# schematic1.net
KiCad netlist of a schematic drawn in EAGLE
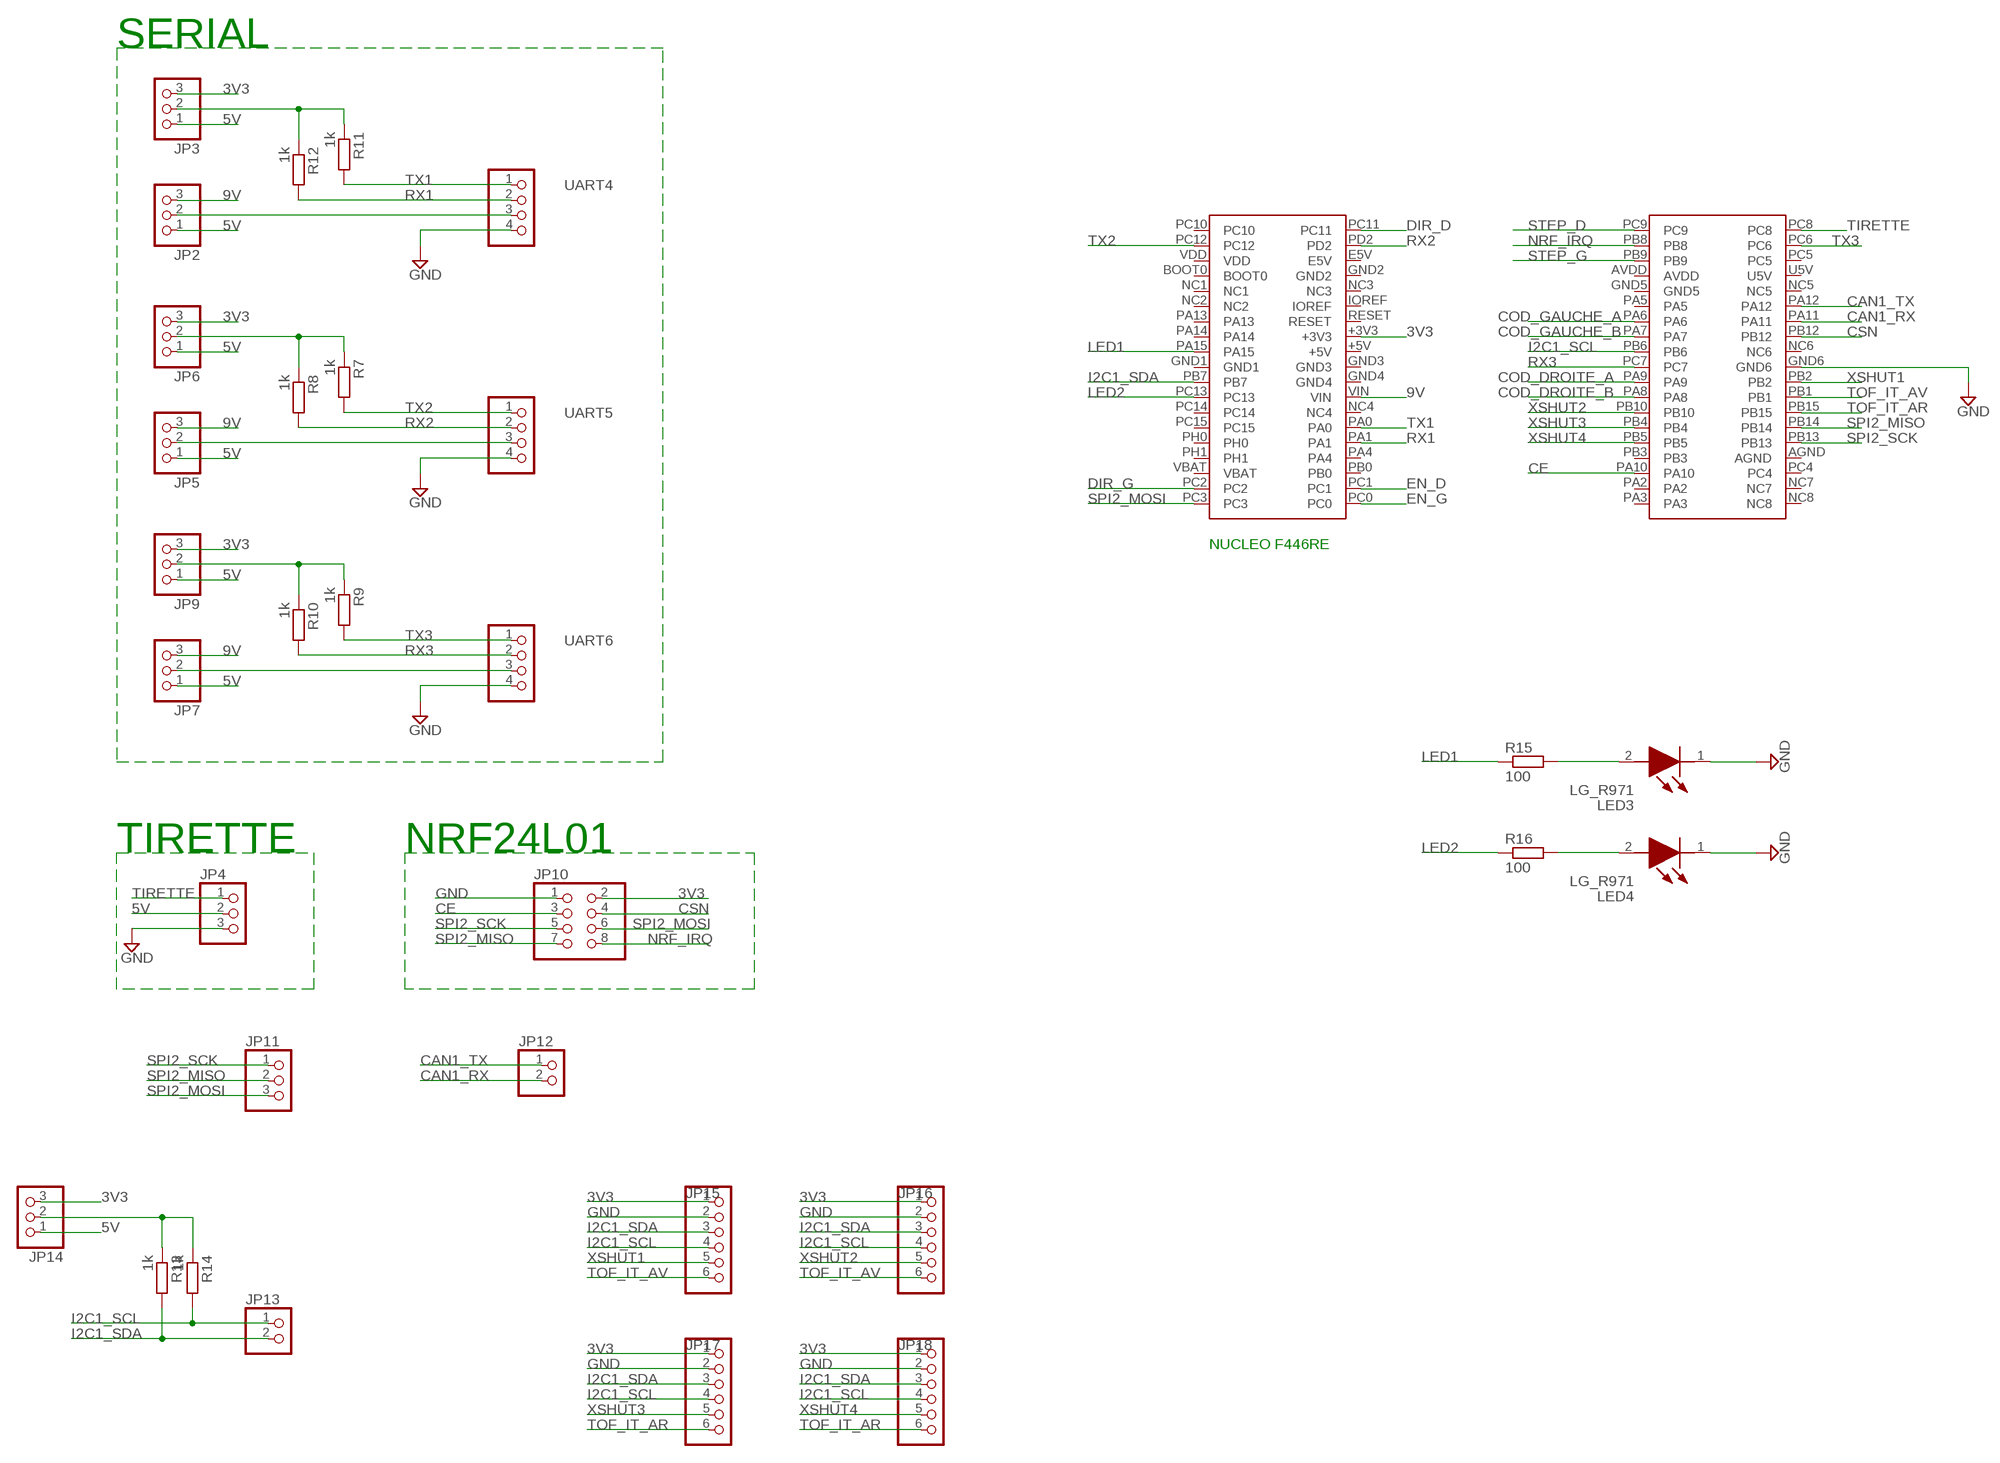
[diagram p0: schematic, sheet 1]
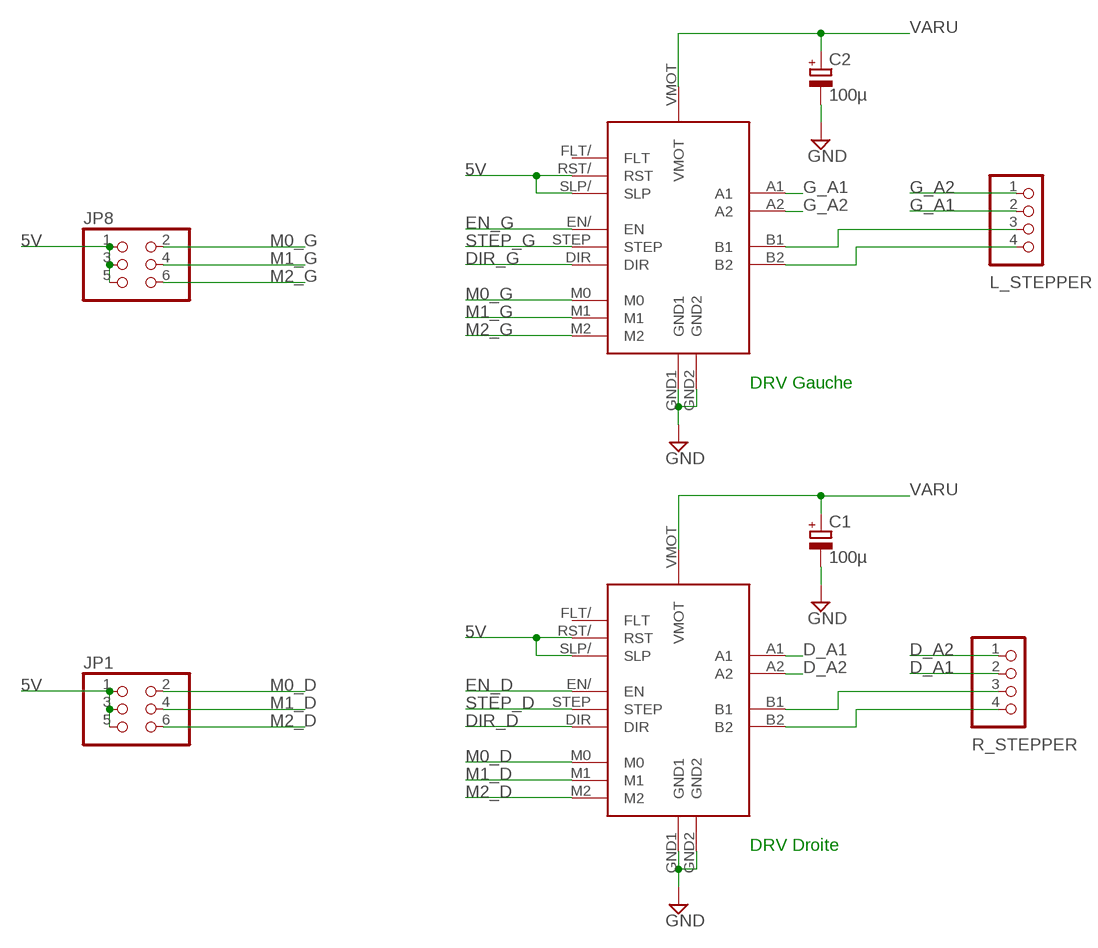
[diagram p1: schematic, sheet 2]
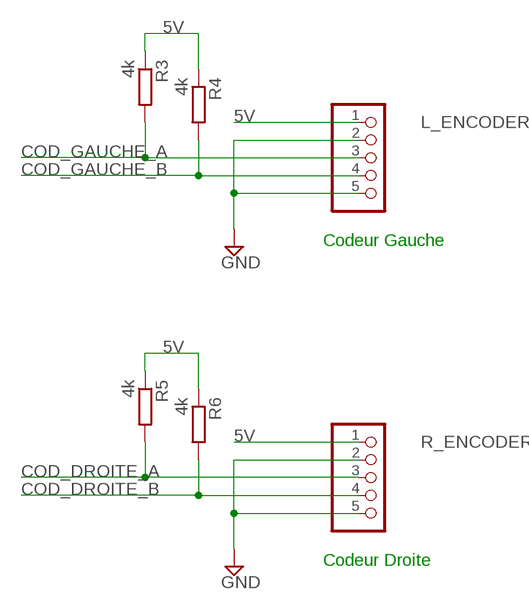
[diagram p2: schematic, sheet 3]
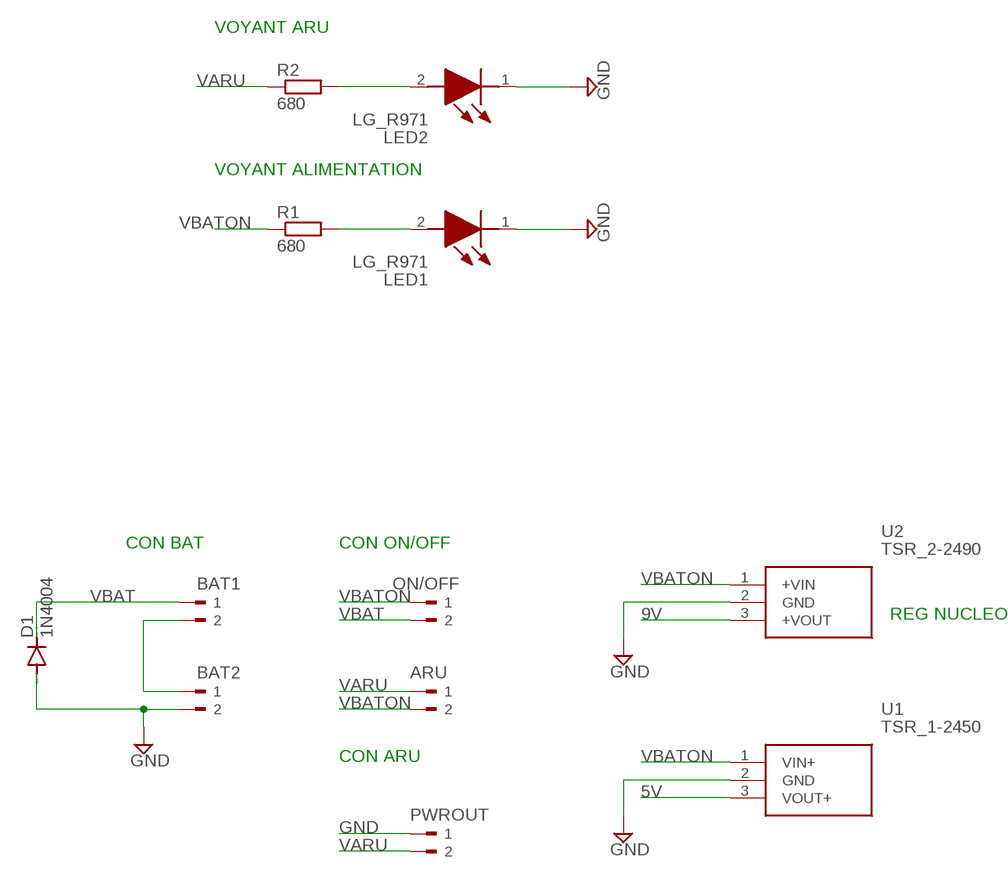
[diagram p3: schematic, sheet 4]

(export (version "E")
  (design (tool "Eeschema 10.0.6"))
  (components
    (comp (ref "JP2")
      (value "PINHD-1X3")
      (footprint "eagle-import:1X03")
      (libsource (lib "eagle-import") (part "PINHD-1X3"))
    )
    (comp (ref "JP3")
      (value "PINHD-1X3")
      (footprint "eagle-import:1X03")
      (libsource (lib "eagle-import") (part "PINHD-1X3"))
    )
    (comp (ref "JP4")
      (value "PINHD-1X3")
      (footprint "eagle-import:1X03")
      (libsource (lib "eagle-import") (part "PINHD-1X3"))
    )
    (comp (ref "JP5")
      (value "PINHD-1X3")
      (footprint "eagle-import:1X03")
      (libsource (lib "eagle-import") (part "PINHD-1X3"))
    )
    (comp (ref "JP6")
      (value "PINHD-1X3")
      (footprint "eagle-import:1X03")
      (libsource (lib "eagle-import") (part "PINHD-1X3"))
    )
    (comp (ref "JP7")
      (value "PINHD-1X3")
      (footprint "eagle-import:1X03")
      (libsource (lib "eagle-import") (part "PINHD-1X3"))
    )
    (comp (ref "JP9")
      (value "PINHD-1X3")
      (footprint "eagle-import:1X03")
      (libsource (lib "eagle-import") (part "PINHD-1X3"))
    )
    (comp (ref "JP10")
      (value "PINHD-2X4")
      (footprint "eagle-import:2X04")
      (libsource (lib "eagle-import") (part "PINHD-2X4"))
    )
    (comp (ref "JP11")
      (value "PINHD-1X3")
      (footprint "eagle-import:1X03")
      (libsource (lib "eagle-import") (part "PINHD-1X3"))
    )
    (comp (ref "JP12")
      (value "PINHD-1X2")
      (footprint "eagle-import:1X02")
      (libsource (lib "eagle-import") (part "PINHD-1X2"))
    )
    (comp (ref "JP13")
      (value "PINHD-1X2")
      (footprint "eagle-import:1X02")
      (libsource (lib "eagle-import") (part "PINHD-1X2"))
    )
    (comp (ref "JP14")
      (value "PINHD-1X3")
      (footprint "eagle-import:1X03")
      (libsource (lib "eagle-import") (part "PINHD-1X3"))
    )
    (comp (ref "JP15")
      (value "PINHD-1X6")
      (footprint "eagle-import:1X06")
      (libsource (lib "eagle-import") (part "PINHD-1X6"))
    )
    (comp (ref "JP16")
      (value "PINHD-1X6")
      (footprint "eagle-import:1X06")
      (libsource (lib "eagle-import") (part "PINHD-1X6"))
    )
    (comp (ref "JP17")
      (value "PINHD-1X6")
      (footprint "eagle-import:1X06")
      (libsource (lib "eagle-import") (part "PINHD-1X6"))
    )
    (comp (ref "JP18")
      (value "PINHD-1X6")
      (footprint "eagle-import:1X06")
      (libsource (lib "eagle-import") (part "PINHD-1X6"))
    )
    (comp (ref "LED3")
      (value "LG_R971")
      (footprint "eagle-import:LEDC2012X90N")
      (fields (field (name "MANUFACTURER_PART_NUMBER") "LG R971") (field (name "RS_PART_NUMBER") "6545773P"))
      (libsource (lib "eagle-import") (part "LG_R971"))
    )
    (comp (ref "LED4")
      (value "LG_R971")
      (footprint "eagle-import:LEDC2012X90N")
      (fields (field (name "MANUFACTURER_PART_NUMBER") "LG R971") (field (name "RS_PART_NUMBER") "6545773P"))
      (libsource (lib "eagle-import") (part "LG_R971"))
    )
    (comp (ref "R7")
      (value "1k")
      (footprint "eagle-import:R0805")
      (libsource (lib "eagle-import") (part "R-EU_R0805"))
    )
    (comp (ref "R8")
      (value "1k")
      (footprint "eagle-import:R0805")
      (libsource (lib "eagle-import") (part "R-EU_R0805"))
    )
    (comp (ref "R9")
      (value "1k")
      (footprint "eagle-import:R0805")
      (libsource (lib "eagle-import") (part "R-EU_R0805"))
    )
    (comp (ref "R10")
      (value "1k")
      (footprint "eagle-import:R0805")
      (libsource (lib "eagle-import") (part "R-EU_R0805"))
    )
    (comp (ref "R11")
      (value "1k")
      (footprint "eagle-import:R0805")
      (libsource (lib "eagle-import") (part "R-EU_R0805"))
    )
    (comp (ref "R12")
      (value "1k")
      (footprint "eagle-import:R0805")
      (libsource (lib "eagle-import") (part "R-EU_R0805"))
    )
    (comp (ref "R13")
      (value "1k")
      (footprint "eagle-import:R0805")
      (libsource (lib "eagle-import") (part "R-EU_R0805"))
    )
    (comp (ref "R14")
      (value "1k")
      (footprint "eagle-import:R0805")
      (libsource (lib "eagle-import") (part "R-EU_R0805"))
    )
    (comp (ref "R15")
      (value "100")
      (footprint "eagle-import:R0805")
      (libsource (lib "eagle-import") (part "R-EU_R0805"))
    )
    (comp (ref "R16")
      (value "100")
      (footprint "eagle-import:R0805")
      (libsource (lib "eagle-import") (part "R-EU_R0805"))
    )
    (comp (ref "U$1")
      (value "NUCLEO_F446RE")
      (footprint "eagle-import:MB1136")
      (libsource (lib "eagle-import") (part "NUCLEO_F446RE"))
    )
    (comp (ref "UART4")
      (value "PINHD-1X4")
      (footprint "eagle-import:1X04")
      (libsource (lib "eagle-import") (part "PINHD-1X4"))
    )
    (comp (ref "UART5")
      (value "PINHD-1X4")
      (footprint "eagle-import:1X04")
      (libsource (lib "eagle-import") (part "PINHD-1X4"))
    )
    (comp (ref "UART6")
      (value "PINHD-1X4")
      (footprint "eagle-import:1X04")
      (libsource (lib "eagle-import") (part "PINHD-1X4"))
    )
    (comp (ref "L_ENCODER")
      (value "PINHD-1X5")
      (footprint "eagle-import:1X05")
      (libsource (lib "eagle-import") (part "PINHD-1X5"))
    )
    (comp (ref "R3")
      (value "4k")
      (footprint "eagle-import:R0805")
      (libsource (lib "eagle-import") (part "R-EU_R0805"))
    )
    (comp (ref "R4")
      (value "4k")
      (footprint "eagle-import:R0805")
      (libsource (lib "eagle-import") (part "R-EU_R0805"))
    )
    (comp (ref "R5")
      (value "4k")
      (footprint "eagle-import:R0805")
      (libsource (lib "eagle-import") (part "R-EU_R0805"))
    )
    (comp (ref "R6")
      (value "4k")
      (footprint "eagle-import:R0805")
      (libsource (lib "eagle-import") (part "R-EU_R0805"))
    )
    (comp (ref "R_ENCODER")
      (value "PINHD-1X5")
      (footprint "eagle-import:1X05")
      (libsource (lib "eagle-import") (part "PINHD-1X5"))
    )
    (comp (ref "ARU")
      (value "180G-2")
      (footprint "eagle-import:180G-2")
      (libsource (lib "eagle-import") (part "180G-2"))
    )
    (comp (ref "BAT1")
      (value "180G-2")
      (footprint "eagle-import:180G-2")
      (libsource (lib "eagle-import") (part "180G-2"))
    )
    (comp (ref "BAT2")
      (value "180G-2")
      (footprint "eagle-import:180G-2")
      (libsource (lib "eagle-import") (part "180G-2"))
    )
    (comp (ref "D1")
      (value "1N4004")
      (footprint "eagle-import:DO41-10")
      (libsource (lib "eagle-import") (part "1N4004"))
    )
    (comp (ref "LED1")
      (value "LG_R971")
      (footprint "eagle-import:LEDC2012X90N")
      (fields (field (name "MANUFACTURER_PART_NUMBER") "LG R971") (field (name "RS_PART_NUMBER") "6545773P"))
      (libsource (lib "eagle-import") (part "LG_R971"))
    )
    (comp (ref "LED2")
      (value "LG_R971")
      (footprint "eagle-import:LEDC2012X90N")
      (fields (field (name "MANUFACTURER_PART_NUMBER") "LG R971") (field (name "RS_PART_NUMBER") "6545773P"))
      (libsource (lib "eagle-import") (part "LG_R971"))
    )
    (comp (ref "ON/OFF")
      (value "180G-2")
      (footprint "eagle-import:180G-2")
      (libsource (lib "eagle-import") (part "180G-2"))
    )
    (comp (ref "PWROUT")
      (value "180G-2")
      (footprint "eagle-import:180G-2")
      (libsource (lib "eagle-import") (part "180G-2"))
    )
    (comp (ref "R1")
      (value "680")
      (footprint "eagle-import:R0805")
      (libsource (lib "eagle-import") (part "R-EU_R0805"))
    )
    (comp (ref "R2")
      (value "680")
      (footprint "eagle-import:R0805")
      (libsource (lib "eagle-import") (part "R-EU_R0805"))
    )
    (comp (ref "U1")
      (value "TSR_1-2450")
      (footprint "eagle-import:TSR-1-24120")
      (fields
        (field (name "MANUFACTURER_PART_NUMBER") "TSR 1-2450")
        (field (name "RS_PART_NUMBER") "6664379P")
      )
      (libsource (lib "eagle-import") (part "TSR_1-2450"))
    )
    (comp (ref "U2")
      (value "TSR_2-2490")
      (footprint "eagle-import:TSR_2-24XX")
      (fields
        (field (name "MANUFACTURER_PART_NUMBER") "TSR 2-2490")
        (field (name "MOUSER_PART_NUMBER") "495-TSR2-2490")
      )
      (libsource (lib "eagle-import") (part "TSR_2-2490"))
    )
    (comp (ref "C1")
      (value "100µ")
      (footprint "eagle-import:E5-6")
      (libsource (lib "eagle-import") (part "CPOL-EUE5-6"))
    )
    (comp (ref "C2")
      (value "100µ")
      (footprint "eagle-import:E5-6")
      (libsource (lib "eagle-import") (part "CPOL-EUE5-6"))
    )
    (comp (ref "JP1")
      (value "PINHD-2X3")
      (footprint "eagle-import:2X03")
      (libsource (lib "eagle-import") (part "PINHD-2X3"))
    )
    (comp (ref "JP8")
      (value "PINHD-2X3")
      (footprint "eagle-import:2X03")
      (libsource (lib "eagle-import") (part "PINHD-2X3"))
    )
    (comp (ref "L_STEPPER")
      (value "PINHD-1X4")
      (footprint "eagle-import:1X04")
      (libsource (lib "eagle-import") (part "PINHD-1X4"))
    )
    (comp (ref "R_STEPPER")
      (value "PINHD-1X4")
      (footprint "eagle-import:1X04")
      (libsource (lib "eagle-import") (part "PINHD-1X4"))
    )
    (comp (ref "U$2")
      (value "POLOLU_DRV8825")
      (footprint "eagle-import:POLOLU_DRV8825")
      (libsource (lib "eagle-import") (part "POLOLU_DRV8825"))
    )
    (comp (ref "U$3")
      (value "POLOLU_DRV8825")
      (footprint "eagle-import:POLOLU_DRV8825")
      (libsource (lib "eagle-import") (part "POLOLU_DRV8825"))
    )
  )
  (nets
    (net (code "1") (name "3V3") (class "Default")
      (node (ref "JP10") (pin "2") (pinfunction "2_2") (pintype "passive"))
      (node (ref "JP14") (pin "3") (pinfunction "3_3") (pintype "passive"))
      (node (ref "JP15") (pin "1") (pinfunction "1_1") (pintype "passive"))
      (node (ref "JP16") (pin "1") (pinfunction "1_1") (pintype "passive"))
      (node (ref "JP17") (pin "1") (pinfunction "1_1") (pintype "passive"))
      (node (ref "JP18") (pin "1") (pinfunction "1_1") (pintype "passive"))
      (node (ref "JP3") (pin "3") (pinfunction "3_3") (pintype "passive"))
      (node (ref "JP6") (pin "3") (pinfunction "3_3") (pintype "passive"))
      (node (ref "JP9") (pin "3") (pinfunction "3_3") (pintype "passive"))
      (node (ref "U$1") (pin "+3V3") (pinfunction "+3V3_+3V3") (pintype "bidirectional"))
    )
    (net (code "2") (name "5V") (class "Default")
      (node (ref "JP1") (pin "1") (pinfunction "1_1") (pintype "passive"))
      (node (ref "JP1") (pin "3") (pinfunction "3_3") (pintype "passive"))
      (node (ref "JP1") (pin "5") (pinfunction "5_5") (pintype "passive"))
      (node (ref "JP14") (pin "1") (pinfunction "1_1") (pintype "passive"))
      (node (ref "JP2") (pin "1") (pinfunction "1_1") (pintype "passive"))
      (node (ref "JP3") (pin "1") (pinfunction "1_1") (pintype "passive"))
      (node (ref "JP4") (pin "2") (pinfunction "2_2") (pintype "passive"))
      (node (ref "JP5") (pin "1") (pinfunction "1_1") (pintype "passive"))
      (node (ref "JP6") (pin "1") (pinfunction "1_1") (pintype "passive"))
      (node (ref "JP7") (pin "1") (pinfunction "1_1") (pintype "passive"))
      (node (ref "JP8") (pin "1") (pinfunction "1_1") (pintype "passive"))
      (node (ref "JP8") (pin "3") (pinfunction "3_3") (pintype "passive"))
      (node (ref "JP8") (pin "5") (pinfunction "5_5") (pintype "passive"))
      (node (ref "JP9") (pin "1") (pinfunction "1_1") (pintype "passive"))
      (node (ref "L_ENCODER") (pin "1") (pinfunction "1_1") (pintype "passive"))
      (node (ref "R3") (pin "1") (pinfunction "1_1") (pintype "passive"))
      (node (ref "R4") (pin "1") (pinfunction "1_1") (pintype "passive"))
      (node (ref "R5") (pin "1") (pinfunction "1_1") (pintype "passive"))
      (node (ref "R6") (pin "1") (pinfunction "1_1") (pintype "passive"))
      (node (ref "R_ENCODER") (pin "1") (pinfunction "1_1") (pintype "passive"))
      (node (ref "U$2") (pin "RST/") (pinfunction "RST_RST/") (pintype "bidirectional"))
      (node (ref "U$2") (pin "SLP/") (pinfunction "SLP_SLP/") (pintype "bidirectional"))
      (node (ref "U$3") (pin "RST/") (pinfunction "RST_RST/") (pintype "bidirectional"))
      (node (ref "U$3") (pin "SLP/") (pinfunction "SLP_SLP/") (pintype "bidirectional"))
      (node (ref "U1") (pin "3") (pinfunction "VOUT+_3") (pintype "input"))
    )
    (net (code "3") (name "9V") (class "Default")
      (node (ref "JP2") (pin "3") (pinfunction "3_3") (pintype "passive"))
      (node (ref "JP5") (pin "3") (pinfunction "3_3") (pintype "passive"))
      (node (ref "JP7") (pin "3") (pinfunction "3_3") (pintype "passive"))
      (node (ref "U$1") (pin "VIN") (pinfunction "VIN_VIN") (pintype "bidirectional"))
      (node (ref "U2") (pin "3") (pinfunction "+VOUT_3") (pintype "bidirectional"))
    )
    (net (code "4") (name "CAN1_RX") (class "Default")
      (node (ref "JP12") (pin "2") (pinfunction "2_2") (pintype "passive"))
      (node (ref "U$1") (pin "PA11") (pinfunction "PA11_PA11") (pintype "bidirectional"))
    )
    (net (code "5") (name "CAN1_TX") (class "Default")
      (node (ref "JP12") (pin "1") (pinfunction "1_1") (pintype "passive"))
      (node (ref "U$1") (pin "PA12") (pinfunction "PA12_PA12") (pintype "bidirectional"))
    )
    (net (code "6") (name "CE") (class "Default")
      (node (ref "JP10") (pin "3") (pinfunction "3_3") (pintype "passive"))
      (node (ref "U$1") (pin "PA10") (pinfunction "PA10_PA10") (pintype "bidirectional"))
    )
    (net (code "7") (name "COD_DROITE_A") (class "Default")
      (node (ref "R5") (pin "2") (pinfunction "2_2") (pintype "passive"))
      (node (ref "R_ENCODER") (pin "3") (pinfunction "3_3") (pintype "passive"))
      (node (ref "U$1") (pin "PA9") (pinfunction "PA9_PA9") (pintype "bidirectional"))
    )
    (net (code "8") (name "COD_DROITE_B") (class "Default")
      (node (ref "R6") (pin "2") (pinfunction "2_2") (pintype "passive"))
      (node (ref "R_ENCODER") (pin "4") (pinfunction "4_4") (pintype "passive"))
      (node (ref "U$1") (pin "PA8") (pinfunction "PA8_PA8") (pintype "bidirectional"))
    )
    (net (code "9") (name "COD_GAUCHE_A") (class "Default")
      (node (ref "L_ENCODER") (pin "3") (pinfunction "3_3") (pintype "passive"))
      (node (ref "R3") (pin "2") (pinfunction "2_2") (pintype "passive"))
      (node (ref "U$1") (pin "PA6") (pinfunction "PA6_PA6") (pintype "bidirectional"))
    )
    (net (code "10") (name "COD_GAUCHE_B") (class "Default")
      (node (ref "L_ENCODER") (pin "4") (pinfunction "4_4") (pintype "passive"))
      (node (ref "R4") (pin "2") (pinfunction "2_2") (pintype "passive"))
      (node (ref "U$1") (pin "PA7") (pinfunction "PA7_PA7") (pintype "bidirectional"))
    )
    (net (code "11") (name "CSN") (class "Default")
      (node (ref "JP10") (pin "4") (pinfunction "4_4") (pintype "passive"))
      (node (ref "U$1") (pin "PB12") (pinfunction "PB12_PB12") (pintype "bidirectional"))
    )
    (net (code "12") (name "DIR_D") (class "Default")
      (node (ref "U$1") (pin "PC11") (pinfunction "PC11_PC11") (pintype "bidirectional"))
      (node (ref "U$3") (pin "DIR") (pinfunction "DIR_DIR") (pintype "bidirectional"))
    )
    (net (code "13") (name "DIR_G") (class "Default")
      (node (ref "U$1") (pin "PC2") (pinfunction "PC2_PC2") (pintype "bidirectional"))
      (node (ref "U$2") (pin "DIR") (pinfunction "DIR_DIR") (pintype "bidirectional"))
    )
    (net (code "14") (name "D_A1") (class "Default")
      (node (ref "R_STEPPER") (pin "2") (pinfunction "2_2") (pintype "passive"))
      (node (ref "U$3") (pin "A1") (pinfunction "A1_A1") (pintype "bidirectional"))
    )
    (net (code "15") (name "D_A2") (class "Default")
      (node (ref "R_STEPPER") (pin "1") (pinfunction "1_1") (pintype "passive"))
      (node (ref "U$3") (pin "A2") (pinfunction "A2_A2") (pintype "bidirectional"))
    )
    (net (code "16") (name "EN_D") (class "Default")
      (node (ref "U$1") (pin "PC1") (pinfunction "PC1_PC1") (pintype "bidirectional"))
      (node (ref "U$3") (pin "EN/") (pinfunction "EN_EN/") (pintype "bidirectional"))
    )
    (net (code "17") (name "EN_G") (class "Default")
      (node (ref "U$1") (pin "PC0") (pinfunction "PC0_PC0") (pintype "bidirectional"))
      (node (ref "U$2") (pin "EN/") (pinfunction "EN_EN/") (pintype "bidirectional"))
    )
    (net (code "18") (name "GND") (class "Default")
      (node (ref "BAT2") (pin "2") (pinfunction "2_2") (pintype "passive"))
      (node (ref "C1") (pin "-") (pinfunction "-_-") (pintype "passive"))
      (node (ref "C2") (pin "-") (pinfunction "-_-") (pintype "passive"))
      (node (ref "D1") (pin "A") (pinfunction "A_A") (pintype "passive"))
      (node (ref "JP10") (pin "1") (pinfunction "1_1") (pintype "passive"))
      (node (ref "JP15") (pin "2") (pinfunction "2_2") (pintype "passive"))
      (node (ref "JP16") (pin "2") (pinfunction "2_2") (pintype "passive"))
      (node (ref "JP17") (pin "2") (pinfunction "2_2") (pintype "passive"))
      (node (ref "JP18") (pin "2") (pinfunction "2_2") (pintype "passive"))
      (node (ref "JP4") (pin "3") (pinfunction "3_3") (pintype "passive"))
      (node (ref "LED1") (pin "1") (pinfunction "K_1") (pintype "bidirectional"))
      (node (ref "LED2") (pin "1") (pinfunction "K_1") (pintype "bidirectional"))
      (node (ref "LED3") (pin "1") (pinfunction "K_1") (pintype "bidirectional"))
      (node (ref "LED4") (pin "1") (pinfunction "K_1") (pintype "bidirectional"))
      (node (ref "L_ENCODER") (pin "2") (pinfunction "2_2") (pintype "passive"))
      (node (ref "L_ENCODER") (pin "5") (pinfunction "5_5") (pintype "passive"))
      (node (ref "PWROUT") (pin "1") (pinfunction "1_1") (pintype "passive"))
      (node (ref "R_ENCODER") (pin "2") (pinfunction "2_2") (pintype "passive"))
      (node (ref "R_ENCODER") (pin "5") (pinfunction "5_5") (pintype "passive"))
      (node (ref "U$1") (pin "GND6") (pinfunction "GND6_GND6") (pintype "bidirectional"))
      (node (ref "U$2") (pin "GND1") (pinfunction "GND1_GND1") (pintype "bidirectional"))
      (node (ref "U$2") (pin "GND2") (pinfunction "GND2_GND2") (pintype "bidirectional"))
      (node (ref "U$3") (pin "GND1") (pinfunction "GND1_GND1") (pintype "bidirectional"))
      (node (ref "U$3") (pin "GND2") (pinfunction "GND2_GND2") (pintype "bidirectional"))
      (node (ref "U1") (pin "2") (pinfunction "GND_2") (pintype "power_in"))
      (node (ref "U2") (pin "2") (pinfunction "GND_2") (pintype "bidirectional"))
      (node (ref "UART4") (pin "4") (pinfunction "4_4") (pintype "passive"))
      (node (ref "UART5") (pin "4") (pinfunction "4_4") (pintype "passive"))
      (node (ref "UART6") (pin "4") (pinfunction "4_4") (pintype "passive"))
    )
    (net (code "19") (name "G_A1") (class "Default")
      (node (ref "L_STEPPER") (pin "2") (pinfunction "2_2") (pintype "passive"))
      (node (ref "U$2") (pin "A1") (pinfunction "A1_A1") (pintype "bidirectional"))
    )
    (net (code "20") (name "G_A2") (class "Default")
      (node (ref "L_STEPPER") (pin "1") (pinfunction "1_1") (pintype "passive"))
      (node (ref "U$2") (pin "A2") (pinfunction "A2_A2") (pintype "bidirectional"))
    )
    (net (code "21") (name "I2C1_SCL") (class "Default")
      (node (ref "JP13") (pin "1") (pinfunction "1_1") (pintype "passive"))
      (node (ref "JP15") (pin "4") (pinfunction "4_4") (pintype "passive"))
      (node (ref "JP16") (pin "4") (pinfunction "4_4") (pintype "passive"))
      (node (ref "JP17") (pin "4") (pinfunction "4_4") (pintype "passive"))
      (node (ref "JP18") (pin "4") (pinfunction "4_4") (pintype "passive"))
      (node (ref "R14") (pin "2") (pinfunction "2_2") (pintype "passive"))
      (node (ref "U$1") (pin "PB6") (pinfunction "PB6_PB6") (pintype "bidirectional"))
    )
    (net (code "22") (name "I2C1_SDA") (class "Default")
      (node (ref "JP13") (pin "2") (pinfunction "2_2") (pintype "passive"))
      (node (ref "JP15") (pin "3") (pinfunction "3_3") (pintype "passive"))
      (node (ref "JP16") (pin "3") (pinfunction "3_3") (pintype "passive"))
      (node (ref "JP17") (pin "3") (pinfunction "3_3") (pintype "passive"))
      (node (ref "JP18") (pin "3") (pinfunction "3_3") (pintype "passive"))
      (node (ref "R13") (pin "2") (pinfunction "2_2") (pintype "passive"))
      (node (ref "U$1") (pin "PB7") (pinfunction "PB7_PB7") (pintype "bidirectional"))
    )
    (net (code "23") (name "LED1") (class "Default")
      (node (ref "R15") (pin "1") (pinfunction "1_1") (pintype "passive"))
      (node (ref "U$1") (pin "PA15") (pinfunction "PA15_PA15") (pintype "bidirectional"))
    )
    (net (code "24") (name "LED2") (class "Default")
      (node (ref "R16") (pin "1") (pinfunction "1_1") (pintype "passive"))
      (node (ref "U$1") (pin "PC13") (pinfunction "PC13_PC13") (pintype "bidirectional"))
    )
    (net (code "25") (name "M0_D") (class "Default")
      (node (ref "JP1") (pin "2") (pinfunction "2_2") (pintype "passive"))
      (node (ref "U$3") (pin "M0") (pinfunction "M0_M0") (pintype "bidirectional"))
    )
    (net (code "26") (name "M0_G") (class "Default")
      (node (ref "JP8") (pin "2") (pinfunction "2_2") (pintype "passive"))
      (node (ref "U$2") (pin "M0") (pinfunction "M0_M0") (pintype "bidirectional"))
    )
    (net (code "27") (name "M1_D") (class "Default")
      (node (ref "JP1") (pin "4") (pinfunction "4_4") (pintype "passive"))
      (node (ref "U$3") (pin "M1") (pinfunction "M1_M1") (pintype "bidirectional"))
    )
    (net (code "28") (name "M1_G") (class "Default")
      (node (ref "JP8") (pin "4") (pinfunction "4_4") (pintype "passive"))
      (node (ref "U$2") (pin "M1") (pinfunction "M1_M1") (pintype "bidirectional"))
    )
    (net (code "29") (name "M2_D") (class "Default")
      (node (ref "JP1") (pin "6") (pinfunction "6_6") (pintype "passive"))
      (node (ref "U$3") (pin "M2") (pinfunction "M2_M2") (pintype "bidirectional"))
    )
    (net (code "30") (name "M2_G") (class "Default")
      (node (ref "JP8") (pin "6") (pinfunction "6_6") (pintype "passive"))
      (node (ref "U$2") (pin "M2") (pinfunction "M2_M2") (pintype "bidirectional"))
    )
    (net (code "31") (name "NRF_IRQ") (class "Default")
      (node (ref "JP10") (pin "8") (pinfunction "8_8") (pintype "passive"))
      (node (ref "U$1") (pin "PB8") (pinfunction "PB8_PB8") (pintype "bidirectional"))
    )
    (net (code "32") (name "Net-(BAT1-Pad2)") (class "Default")
      (node (ref "BAT1") (pin "2") (pinfunction "2_2") (pintype "passive"))
      (node (ref "BAT2") (pin "1") (pinfunction "1_1") (pintype "passive"))
    )
    (net (code "33") (name "Net-(JP2-Pad2)") (class "Default")
      (node (ref "JP2") (pin "2") (pinfunction "2_2") (pintype "passive"))
      (node (ref "UART4") (pin "3") (pinfunction "3_3") (pintype "passive"))
    )
    (net (code "34") (name "Net-(JP3-Pad2)") (class "Default")
      (node (ref "JP3") (pin "2") (pinfunction "2_2") (pintype "passive"))
      (node (ref "R11") (pin "1") (pinfunction "1_1") (pintype "passive"))
      (node (ref "R12") (pin "1") (pinfunction "1_1") (pintype "passive"))
    )
    (net (code "35") (name "Net-(JP5-Pad2)") (class "Default")
      (node (ref "JP5") (pin "2") (pinfunction "2_2") (pintype "passive"))
      (node (ref "UART5") (pin "3") (pinfunction "3_3") (pintype "passive"))
    )
    (net (code "36") (name "Net-(JP6-Pad2)") (class "Default")
      (node (ref "JP6") (pin "2") (pinfunction "2_2") (pintype "passive"))
      (node (ref "R7") (pin "1") (pinfunction "1_1") (pintype "passive"))
      (node (ref "R8") (pin "1") (pinfunction "1_1") (pintype "passive"))
    )
    (net (code "37") (name "Net-(JP7-Pad2)") (class "Default")
      (node (ref "JP7") (pin "2") (pinfunction "2_2") (pintype "passive"))
      (node (ref "UART6") (pin "3") (pinfunction "3_3") (pintype "passive"))
    )
    (net (code "38") (name "Net-(JP9-Pad2)") (class "Default")
      (node (ref "JP9") (pin "2") (pinfunction "2_2") (pintype "passive"))
      (node (ref "R10") (pin "1") (pinfunction "1_1") (pintype "passive"))
      (node (ref "R9") (pin "1") (pinfunction "1_1") (pintype "passive"))
    )
    (net (code "39") (name "Net-(JP14-Pad2)") (class "Default")
      (node (ref "JP14") (pin "2") (pinfunction "2_2") (pintype "passive"))
      (node (ref "R13") (pin "1") (pinfunction "1_1") (pintype "passive"))
      (node (ref "R14") (pin "1") (pinfunction "1_1") (pintype "passive"))
    )
    (net (code "40") (name "Net-(LED1-A)") (class "Default")
      (node (ref "LED1") (pin "2") (pinfunction "A_2") (pintype "bidirectional"))
      (node (ref "R1") (pin "2") (pinfunction "2_2") (pintype "passive"))
    )
    (net (code "41") (name "Net-(LED2-A)") (class "Default")
      (node (ref "LED2") (pin "2") (pinfunction "A_2") (pintype "bidirectional"))
      (node (ref "R2") (pin "2") (pinfunction "2_2") (pintype "passive"))
    )
    (net (code "42") (name "Net-(LED3-A)") (class "Default")
      (node (ref "LED3") (pin "2") (pinfunction "A_2") (pintype "bidirectional"))
      (node (ref "R15") (pin "2") (pinfunction "2_2") (pintype "passive"))
    )
    (net (code "43") (name "Net-(LED4-A)") (class "Default")
      (node (ref "LED4") (pin "2") (pinfunction "A_2") (pintype "bidirectional"))
      (node (ref "R16") (pin "2") (pinfunction "2_2") (pintype "passive"))
    )
    (net (code "44") (name "Net-(L_STEPPER-Pad3)") (class "Default")
      (node (ref "L_STEPPER") (pin "3") (pinfunction "3_3") (pintype "passive"))
      (node (ref "U$2") (pin "B1") (pinfunction "B1_B1") (pintype "bidirectional"))
    )
    (net (code "45") (name "Net-(L_STEPPER-Pad4)") (class "Default")
      (node (ref "L_STEPPER") (pin "4") (pinfunction "4_4") (pintype "passive"))
      (node (ref "U$2") (pin "B2") (pinfunction "B2_B2") (pintype "bidirectional"))
    )
    (net (code "46") (name "Net-(R_STEPPER-Pad3)") (class "Default")
      (node (ref "R_STEPPER") (pin "3") (pinfunction "3_3") (pintype "passive"))
      (node (ref "U$3") (pin "B1") (pinfunction "B1_B1") (pintype "bidirectional"))
    )
    (net (code "47") (name "Net-(R_STEPPER-Pad4)") (class "Default")
      (node (ref "R_STEPPER") (pin "4") (pinfunction "4_4") (pintype "passive"))
      (node (ref "U$3") (pin "B2") (pinfunction "B2_B2") (pintype "bidirectional"))
    )
    (net (code "48") (name "RX1") (class "Default")
      (node (ref "R12") (pin "2") (pinfunction "2_2") (pintype "passive"))
      (node (ref "U$1") (pin "PA1") (pinfunction "PA1_PA1") (pintype "bidirectional"))
      (node (ref "UART4") (pin "2") (pinfunction "2_2") (pintype "passive"))
    )
    (net (code "49") (name "RX2") (class "Default")
      (node (ref "R8") (pin "2") (pinfunction "2_2") (pintype "passive"))
      (node (ref "U$1") (pin "PD2") (pinfunction "PD2_PD2") (pintype "bidirectional"))
      (node (ref "UART5") (pin "2") (pinfunction "2_2") (pintype "passive"))
    )
    (net (code "50") (name "RX3") (class "Default")
      (node (ref "R10") (pin "2") (pinfunction "2_2") (pintype "passive"))
      (node (ref "U$1") (pin "PC7") (pinfunction "PC7_PC7") (pintype "bidirectional"))
      (node (ref "UART6") (pin "2") (pinfunction "2_2") (pintype "passive"))
    )
    (net (code "51") (name "SPI2_MISO") (class "Default")
      (node (ref "JP10") (pin "7") (pinfunction "7_7") (pintype "passive"))
      (node (ref "JP11") (pin "2") (pinfunction "2_2") (pintype "passive"))
      (node (ref "U$1") (pin "PB14") (pinfunction "PB14_PB14") (pintype "bidirectional"))
    )
    (net (code "52") (name "SPI2_MOSI") (class "Default")
      (node (ref "JP10") (pin "6") (pinfunction "6_6") (pintype "passive"))
      (node (ref "JP11") (pin "3") (pinfunction "3_3") (pintype "passive"))
      (node (ref "U$1") (pin "PC3") (pinfunction "PC3_PC3") (pintype "bidirectional"))
    )
    (net (code "53") (name "SPI2_SCK") (class "Default")
      (node (ref "JP10") (pin "5") (pinfunction "5_5") (pintype "passive"))
      (node (ref "JP11") (pin "1") (pinfunction "1_1") (pintype "passive"))
      (node (ref "U$1") (pin "PB13") (pinfunction "PB13_PB13") (pintype "bidirectional"))
    )
    (net (code "54") (name "STEP_D") (class "Default")
      (node (ref "U$1") (pin "PC9") (pinfunction "PC9_PC9") (pintype "bidirectional"))
      (node (ref "U$3") (pin "STEP") (pinfunction "STEP_STEP") (pintype "bidirectional"))
    )
    (net (code "55") (name "STEP_G") (class "Default")
      (node (ref "U$1") (pin "PB9") (pinfunction "PB9_PB9") (pintype "bidirectional"))
      (node (ref "U$2") (pin "STEP") (pinfunction "STEP_STEP") (pintype "bidirectional"))
    )
    (net (code "56") (name "TIRETTE") (class "Default")
      (node (ref "JP4") (pin "1") (pinfunction "1_1") (pintype "passive"))
      (node (ref "U$1") (pin "PC8") (pinfunction "PC8_PC8") (pintype "bidirectional"))
    )
    (net (code "57") (name "TOF_IT_AR") (class "Default")
      (node (ref "JP17") (pin "6") (pinfunction "6_6") (pintype "passive"))
      (node (ref "JP18") (pin "6") (pinfunction "6_6") (pintype "passive"))
      (node (ref "U$1") (pin "PB15") (pinfunction "PB15_PB15") (pintype "bidirectional"))
    )
    (net (code "58") (name "TOF_IT_AV") (class "Default")
      (node (ref "JP15") (pin "6") (pinfunction "6_6") (pintype "passive"))
      (node (ref "JP16") (pin "6") (pinfunction "6_6") (pintype "passive"))
      (node (ref "U$1") (pin "PB1") (pinfunction "PB1_PB1") (pintype "bidirectional"))
    )
    (net (code "59") (name "TX1") (class "Default")
      (node (ref "R11") (pin "2") (pinfunction "2_2") (pintype "passive"))
      (node (ref "U$1") (pin "PA0") (pinfunction "PA0_PA0") (pintype "bidirectional"))
      (node (ref "UART4") (pin "1") (pinfunction "1_1") (pintype "passive"))
    )
    (net (code "60") (name "TX2") (class "Default")
      (node (ref "R7") (pin "2") (pinfunction "2_2") (pintype "passive"))
      (node (ref "U$1") (pin "PC12") (pinfunction "PC12_PC12") (pintype "bidirectional"))
      (node (ref "UART5") (pin "1") (pinfunction "1_1") (pintype "passive"))
    )
    (net (code "61") (name "TX3") (class "Default")
      (node (ref "R9") (pin "2") (pinfunction "2_2") (pintype "passive"))
      (node (ref "U$1") (pin "PC6") (pinfunction "PC6_PC6") (pintype "bidirectional"))
      (node (ref "UART6") (pin "1") (pinfunction "1_1") (pintype "passive"))
    )
    (net (code "62") (name "VARU") (class "Default")
      (node (ref "ARU") (pin "1") (pinfunction "1_1") (pintype "passive"))
      (node (ref "C1") (pin "+") (pinfunction "+_+") (pintype "passive"))
      (node (ref "C2") (pin "+") (pinfunction "+_+") (pintype "passive"))
      (node (ref "PWROUT") (pin "2") (pinfunction "2_2") (pintype "passive"))
      (node (ref "R2") (pin "1") (pinfunction "1_1") (pintype "passive"))
      (node (ref "U$2") (pin "VMOT") (pinfunction "VMOT_VMOT") (pintype "bidirectional"))
      (node (ref "U$3") (pin "VMOT") (pinfunction "VMOT_VMOT") (pintype "bidirectional"))
    )
    (net (code "63") (name "VBAT") (class "Default")
      (node (ref "BAT1") (pin "1") (pinfunction "1_1") (pintype "passive"))
      (node (ref "D1") (pin "C") (pinfunction "C_C") (pintype "passive"))
      (node (ref "ON/OFF") (pin "2") (pinfunction "2_2") (pintype "passive"))
    )
    (net (code "64") (name "VBATON") (class "Default")
      (node (ref "ARU") (pin "2") (pinfunction "2_2") (pintype "passive"))
      (node (ref "ON/OFF") (pin "1") (pinfunction "1_1") (pintype "passive"))
      (node (ref "R1") (pin "1") (pinfunction "1_1") (pintype "passive"))
      (node (ref "U1") (pin "1") (pinfunction "VIN+_1") (pintype "input"))
      (node (ref "U2") (pin "1") (pinfunction "+VIN_1") (pintype "bidirectional"))
    )
    (net (code "65") (name "XSHUT1") (class "Default")
      (node (ref "JP15") (pin "5") (pinfunction "5_5") (pintype "passive"))
      (node (ref "U$1") (pin "PB2") (pinfunction "PB2_PB2") (pintype "bidirectional"))
    )
    (net (code "66") (name "XSHUT2") (class "Default")
      (node (ref "JP16") (pin "5") (pinfunction "5_5") (pintype "passive"))
      (node (ref "U$1") (pin "PB10") (pinfunction "PB10_PB10") (pintype "bidirectional"))
    )
    (net (code "67") (name "XSHUT3") (class "Default")
      (node (ref "JP17") (pin "5") (pinfunction "5_5") (pintype "passive"))
      (node (ref "U$1") (pin "PB4") (pinfunction "PB4_PB4") (pintype "bidirectional"))
    )
    (net (code "68") (name "XSHUT4") (class "Default")
      (node (ref "JP18") (pin "5") (pinfunction "5_5") (pintype "passive"))
      (node (ref "U$1") (pin "PB5") (pinfunction "PB5_PB5") (pintype "bidirectional"))
    )
    (net (code "69") (name "unconnected-(U$1-Pad+5V)") (class "Default")
      (node (ref "U$1") (pin "+5V") (pinfunction "+5V_+5V") (pintype "bidirectional"))
    )
    (net (code "70") (name "unconnected-(U$1-PadAGND)") (class "Default")
      (node (ref "U$1") (pin "AGND") (pinfunction "AGND_AGND") (pintype "bidirectional"))
    )
    (net (code "71") (name "unconnected-(U$1-PadAVDD)") (class "Default")
      (node (ref "U$1") (pin "AVDD") (pinfunction "AVDD_AVDD") (pintype "bidirectional"))
    )
    (net (code "72") (name "unconnected-(U$1-PadBOOT0)") (class "Default")
      (node (ref "U$1") (pin "BOOT0") (pinfunction "BOOT0_BOOT0") (pintype "bidirectional"))
    )
    (net (code "73") (name "unconnected-(U$1-PadE5V)") (class "Default")
      (node (ref "U$1") (pin "E5V") (pinfunction "E5V_E5V") (pintype "bidirectional"))
    )
    (net (code "74") (name "unconnected-(U$1-PadGND1)") (class "Default")
      (node (ref "U$1") (pin "GND1") (pinfunction "GND1_GND1") (pintype "bidirectional"))
    )
    (net (code "75") (name "unconnected-(U$1-PadGND2)") (class "Default")
      (node (ref "U$1") (pin "GND2") (pinfunction "GND2_GND2") (pintype "bidirectional"))
    )
    (net (code "76") (name "unconnected-(U$1-PadGND3)") (class "Default")
      (node (ref "U$1") (pin "GND3") (pinfunction "GND3_GND3") (pintype "bidirectional"))
    )
    (net (code "77") (name "unconnected-(U$1-PadGND4)") (class "Default")
      (node (ref "U$1") (pin "GND4") (pinfunction "GND4_GND4") (pintype "bidirectional"))
    )
    (net (code "78") (name "unconnected-(U$1-PadGND5)") (class "Default")
      (node (ref "U$1") (pin "GND5") (pinfunction "GND5_GND5") (pintype "bidirectional"))
    )
    (net (code "79") (name "unconnected-(U$1-PadIOREF)") (class "Default")
      (node (ref "U$1") (pin "IOREF") (pinfunction "IOREF_IOREF") (pintype "bidirectional"))
    )
    (net (code "80") (name "unconnected-(U$1-PadNC1)") (class "Default")
      (node (ref "U$1") (pin "NC1") (pinfunction "NC1_NC1") (pintype "no_connect"))
    )
    (net (code "81") (name "unconnected-(U$1-PadNC2)") (class "Default")
      (node (ref "U$1") (pin "NC2") (pinfunction "NC2_NC2") (pintype "no_connect"))
    )
    (net (code "82") (name "unconnected-(U$1-PadNC3)") (class "Default")
      (node (ref "U$1") (pin "NC3") (pinfunction "NC3_NC3") (pintype "no_connect"))
    )
    (net (code "83") (name "unconnected-(U$1-PadNC4)") (class "Default")
      (node (ref "U$1") (pin "NC4") (pinfunction "NC4_NC4") (pintype "no_connect"))
    )
    (net (code "84") (name "unconnected-(U$1-PadNC5)") (class "Default")
      (node (ref "U$1") (pin "NC5") (pinfunction "NC5_NC5") (pintype "no_connect"))
    )
    (net (code "85") (name "unconnected-(U$1-PadNC6)") (class "Default")
      (node (ref "U$1") (pin "NC6") (pinfunction "NC6_NC6") (pintype "no_connect"))
    )
    (net (code "86") (name "unconnected-(U$1-PadNC7)") (class "Default")
      (node (ref "U$1") (pin "NC7") (pinfunction "NC7_NC7") (pintype "no_connect"))
    )
    (net (code "87") (name "unconnected-(U$1-PadNC8)") (class "Default")
      (node (ref "U$1") (pin "NC8") (pinfunction "NC8_NC8") (pintype "no_connect"))
    )
    (net (code "88") (name "unconnected-(U$1-PadPA2)") (class "Default")
      (node (ref "U$1") (pin "PA2") (pinfunction "PA2_PA2") (pintype "bidirectional"))
    )
    (net (code "89") (name "unconnected-(U$1-PadPA3)") (class "Default")
      (node (ref "U$1") (pin "PA3") (pinfunction "PA3_PA3") (pintype "bidirectional"))
    )
    (net (code "90") (name "unconnected-(U$1-PadPA4)") (class "Default")
      (node (ref "U$1") (pin "PA4") (pinfunction "PA4_PA4") (pintype "bidirectional"))
    )
    (net (code "91") (name "unconnected-(U$1-PadPA5)") (class "Default")
      (node (ref "U$1") (pin "PA5") (pinfunction "PA5_PA5") (pintype "bidirectional"))
    )
    (net (code "92") (name "unconnected-(U$1-PadPA13)") (class "Default")
      (node (ref "U$1") (pin "PA13") (pinfunction "PA13_PA13") (pintype "bidirectional"))
    )
    (net (code "93") (name "unconnected-(U$1-PadPA14)") (class "Default")
      (node (ref "U$1") (pin "PA14") (pinfunction "PA14_PA14") (pintype "bidirectional"))
    )
    (net (code "94") (name "unconnected-(U$1-PadPB0)") (class "Default")
      (node (ref "U$1") (pin "PB0") (pinfunction "PB0_PB0") (pintype "bidirectional"))
    )
    (net (code "95") (name "unconnected-(U$1-PadPB3)") (class "Default")
      (node (ref "U$1") (pin "PB3") (pinfunction "PB3_PB3") (pintype "bidirectional"))
    )
    (net (code "96") (name "unconnected-(U$1-PadPC4)") (class "Default")
      (node (ref "U$1") (pin "PC4") (pinfunction "PC4_PC4") (pintype "bidirectional"))
    )
    (net (code "97") (name "unconnected-(U$1-PadPC5)") (class "Default")
      (node (ref "U$1") (pin "PC5") (pinfunction "PC5_PC5") (pintype "bidirectional"))
    )
    (net (code "98") (name "unconnected-(U$1-PadPC10)") (class "Default")
      (node (ref "U$1") (pin "PC10") (pinfunction "PC10_PC10") (pintype "bidirectional"))
    )
    (net (code "99") (name "unconnected-(U$1-PadPC14)") (class "Default")
      (node (ref "U$1") (pin "PC14") (pinfunction "PC14_PC14") (pintype "bidirectional"))
    )
    (net (code "100") (name "unconnected-(U$1-PadPC15)") (class "Default")
      (node (ref "U$1") (pin "PC15") (pinfunction "PC15_PC15") (pintype "bidirectional"))
    )
    (net (code "101") (name "unconnected-(U$1-PadPH0)") (class "Default")
      (node (ref "U$1") (pin "PH0") (pinfunction "PH0_PH0") (pintype "bidirectional"))
    )
    (net (code "102") (name "unconnected-(U$1-PadPH1)") (class "Default")
      (node (ref "U$1") (pin "PH1") (pinfunction "PH1_PH1") (pintype "bidirectional"))
    )
    (net (code "103") (name "unconnected-(U$1-PadRESET)") (class "Default")
      (node (ref "U$1") (pin "RESET") (pinfunction "RESET_RESET") (pintype "bidirectional"))
    )
    (net (code "104") (name "unconnected-(U$1-PadU5V)") (class "Default")
      (node (ref "U$1") (pin "U5V") (pinfunction "U5V_U5V") (pintype "bidirectional"))
    )
    (net (code "105") (name "unconnected-(U$1-PadVBAT)") (class "Default")
      (node (ref "U$1") (pin "VBAT") (pinfunction "VBAT_VBAT") (pintype "bidirectional"))
    )
    (net (code "106") (name "unconnected-(U$1-PadVDD)") (class "Default")
      (node (ref "U$1") (pin "VDD") (pinfunction "VDD_VDD") (pintype "bidirectional"))
    )
    (net (code "107") (name "unconnected-(U$2-FLT-PadFLT{slash})") (class "Default")
      (node (ref "U$2") (pin "FLT/") (pinfunction "FLT_FLT/") (pintype "bidirectional"))
    )
    (net (code "108") (name "unconnected-(U$3-FLT-PadFLT{slash})") (class "Default")
      (node (ref "U$3") (pin "FLT/") (pinfunction "FLT_FLT/") (pintype "bidirectional"))
    )
  )
)
